# flashtest.net
KiCad netlist of a schematic drawn in EAGLE
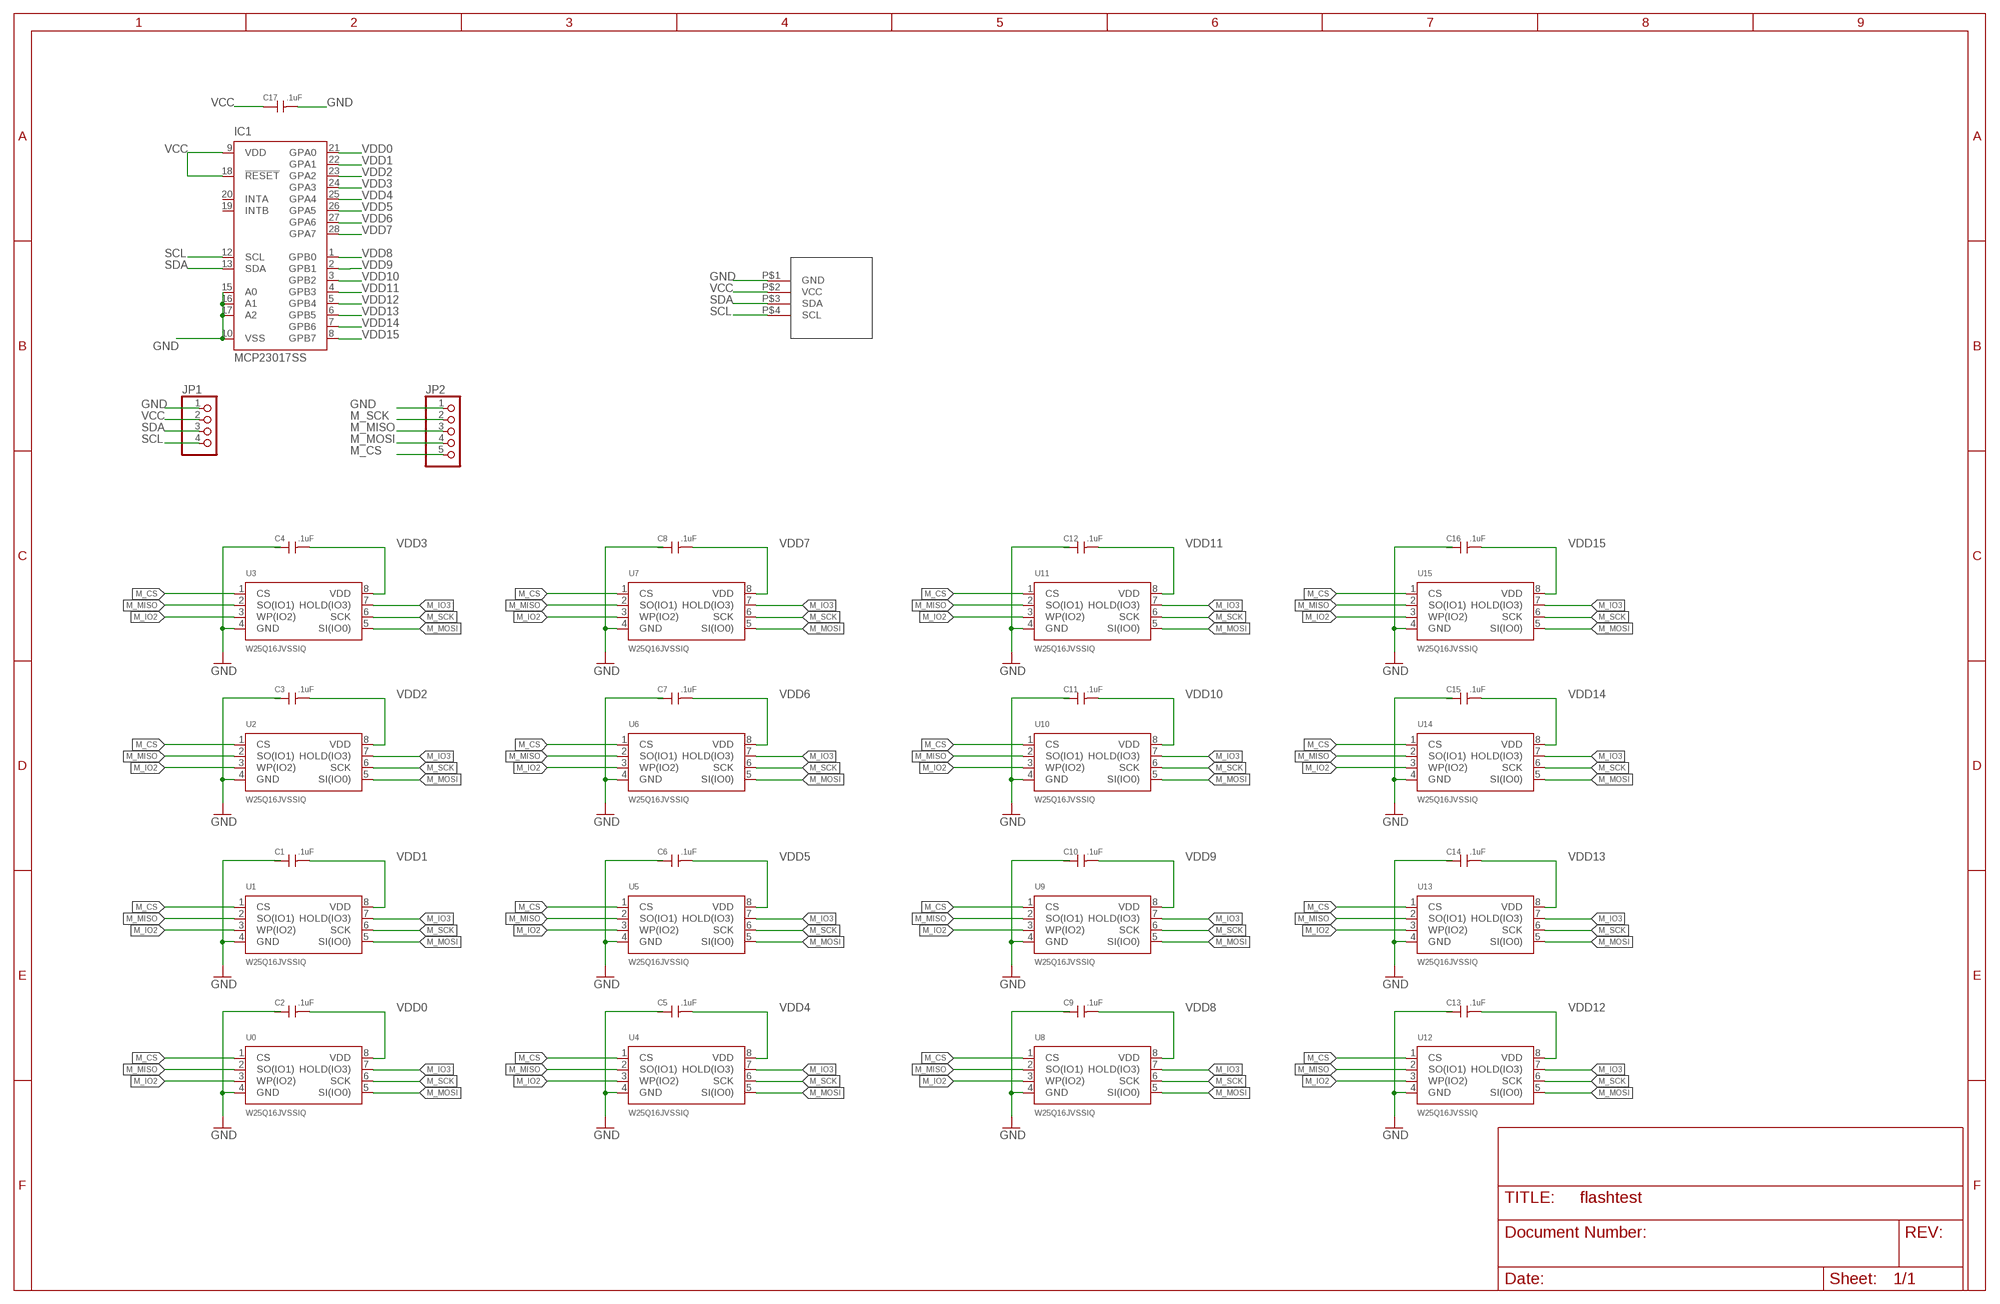
[diagram p0: schematic, sheet 1]

(export (version "E")
  (design (tool "Eeschema 10.0.6"))
  (components
    (comp (ref "C1")
      (value ".1uF")
      (footprint "eagle-import:0603@1")
      (libsource (lib "eagle-import") (part "006-C3540"))
    )
    (comp (ref "C2")
      (value ".1uF")
      (footprint "eagle-import:0603@1")
      (libsource (lib "eagle-import") (part "006-C3540"))
    )
    (comp (ref "C3")
      (value ".1uF")
      (footprint "eagle-import:0603@1")
      (libsource (lib "eagle-import") (part "006-C3540"))
    )
    (comp (ref "C4")
      (value ".1uF")
      (footprint "eagle-import:0603@1")
      (libsource (lib "eagle-import") (part "006-C3540"))
    )
    (comp (ref "C5")
      (value ".1uF")
      (footprint "eagle-import:0603@1")
      (libsource (lib "eagle-import") (part "006-C3540"))
    )
    (comp (ref "C6")
      (value ".1uF")
      (footprint "eagle-import:0603@1")
      (libsource (lib "eagle-import") (part "006-C3540"))
    )
    (comp (ref "C7")
      (value ".1uF")
      (footprint "eagle-import:0603@1")
      (libsource (lib "eagle-import") (part "006-C3540"))
    )
    (comp (ref "C8")
      (value ".1uF")
      (footprint "eagle-import:0603@1")
      (libsource (lib "eagle-import") (part "006-C3540"))
    )
    (comp (ref "C9")
      (value ".1uF")
      (footprint "eagle-import:0603@1")
      (libsource (lib "eagle-import") (part "006-C3540"))
    )
    (comp (ref "C10")
      (value ".1uF")
      (footprint "eagle-import:0603@1")
      (libsource (lib "eagle-import") (part "006-C3540"))
    )
    (comp (ref "C11")
      (value ".1uF")
      (footprint "eagle-import:0603@1")
      (libsource (lib "eagle-import") (part "006-C3540"))
    )
    (comp (ref "C12")
      (value ".1uF")
      (footprint "eagle-import:0603@1")
      (libsource (lib "eagle-import") (part "006-C3540"))
    )
    (comp (ref "C13")
      (value ".1uF")
      (footprint "eagle-import:0603@1")
      (libsource (lib "eagle-import") (part "006-C3540"))
    )
    (comp (ref "C14")
      (value ".1uF")
      (footprint "eagle-import:0603@1")
      (libsource (lib "eagle-import") (part "006-C3540"))
    )
    (comp (ref "C15")
      (value ".1uF")
      (footprint "eagle-import:0603@1")
      (libsource (lib "eagle-import") (part "006-C3540"))
    )
    (comp (ref "C16")
      (value ".1uF")
      (footprint "eagle-import:0603@1")
      (libsource (lib "eagle-import") (part "006-C3540"))
    )
    (comp (ref "C17")
      (value ".1uF")
      (footprint "eagle-import:0603@1")
      (libsource (lib "eagle-import") (part "006-C3540"))
    )
    (comp (ref "IC1")
      (value "MCP23017SS")
      (footprint "eagle-import:SSOP28")
      (fields (field (name "MF") "MICROCHIP") (field (name "MPN") "MCP23017-E/SS"))
      (libsource (lib "eagle-import") (part "MCP23017SS"))
    )
    (comp (ref "JP1")
      (value "PINHD-1X4")
      (footprint "eagle-import:1X04")
      (libsource (lib "eagle-import") (part "PINHD-1X4"))
    )
    (comp (ref "JP2")
      (value "PINHD-1X5")
      (footprint "eagle-import:1X05")
      (libsource (lib "eagle-import") (part "PINHD-1X5"))
    )
    (comp (ref "U$1")
      (value "I2C")
      (footprint "eagle-import:I2C")
      (libsource (lib "eagle-import") (part "I2C"))
    )
    (comp (ref "U0")
      (value "W25Q16JVSSIQ")
      (footprint "eagle-import:SOIC-8")
      (libsource (lib "eagle-import") (part "FLASH_QSPI"))
    )
    (comp (ref "U1")
      (value "W25Q16JVSSIQ")
      (footprint "eagle-import:SOIC-8")
      (libsource (lib "eagle-import") (part "FLASH_QSPI"))
    )
    (comp (ref "U2")
      (value "W25Q16JVSSIQ")
      (footprint "eagle-import:SOIC-8")
      (libsource (lib "eagle-import") (part "FLASH_QSPI"))
    )
    (comp (ref "U3")
      (value "W25Q16JVSSIQ")
      (footprint "eagle-import:SOIC-8")
      (libsource (lib "eagle-import") (part "FLASH_QSPI"))
    )
    (comp (ref "U4")
      (value "W25Q16JVSSIQ")
      (footprint "eagle-import:SOIC-8")
      (libsource (lib "eagle-import") (part "FLASH_QSPI"))
    )
    (comp (ref "U5")
      (value "W25Q16JVSSIQ")
      (footprint "eagle-import:SOIC-8")
      (libsource (lib "eagle-import") (part "FLASH_QSPI"))
    )
    (comp (ref "U6")
      (value "W25Q16JVSSIQ")
      (footprint "eagle-import:SOIC-8")
      (libsource (lib "eagle-import") (part "FLASH_QSPI"))
    )
    (comp (ref "U7")
      (value "W25Q16JVSSIQ")
      (footprint "eagle-import:SOIC-8")
      (libsource (lib "eagle-import") (part "FLASH_QSPI"))
    )
    (comp (ref "U8")
      (value "W25Q16JVSSIQ")
      (footprint "eagle-import:SOIC-8")
      (libsource (lib "eagle-import") (part "FLASH_QSPI"))
    )
    (comp (ref "U9")
      (value "W25Q16JVSSIQ")
      (footprint "eagle-import:SOIC-8")
      (libsource (lib "eagle-import") (part "FLASH_QSPI"))
    )
    (comp (ref "U10")
      (value "W25Q16JVSSIQ")
      (footprint "eagle-import:SOIC-8")
      (libsource (lib "eagle-import") (part "FLASH_QSPI"))
    )
    (comp (ref "U11")
      (value "W25Q16JVSSIQ")
      (footprint "eagle-import:SOIC-8")
      (libsource (lib "eagle-import") (part "FLASH_QSPI"))
    )
    (comp (ref "U12")
      (value "W25Q16JVSSIQ")
      (footprint "eagle-import:SOIC-8")
      (libsource (lib "eagle-import") (part "FLASH_QSPI"))
    )
    (comp (ref "U13")
      (value "W25Q16JVSSIQ")
      (footprint "eagle-import:SOIC-8")
      (libsource (lib "eagle-import") (part "FLASH_QSPI"))
    )
    (comp (ref "U14")
      (value "W25Q16JVSSIQ")
      (footprint "eagle-import:SOIC-8")
      (libsource (lib "eagle-import") (part "FLASH_QSPI"))
    )
    (comp (ref "U15")
      (value "W25Q16JVSSIQ")
      (footprint "eagle-import:SOIC-8")
      (libsource (lib "eagle-import") (part "FLASH_QSPI"))
    )
  )
  (nets
    (net (code "1") (name "/SCL") (class "Default")
      (node (ref "IC1") (pin "12") (pinfunction "SCL_12") (pintype "input"))
      (node (ref "JP1") (pin "4") (pinfunction "4_4") (pintype "passive"))
      (node (ref "U$1") (pin "P$4") (pinfunction "SCL_P$4") (pintype "bidirectional"))
    )
    (net (code "2") (name "/SDA") (class "Default")
      (node (ref "IC1") (pin "13") (pinfunction "SDA_13") (pintype "bidirectional"))
      (node (ref "JP1") (pin "3") (pinfunction "3_3") (pintype "passive"))
      (node (ref "U$1") (pin "P$3") (pinfunction "SDA_P$3") (pintype "bidirectional"))
    )
    (net (code "3") (name "/VCC") (class "Default")
      (node (ref "C17") (pin "1") (pinfunction "1_1") (pintype "passive"))
      (node (ref "IC1") (pin "18") (pinfunction "~{RESET}_18") (pintype "input"))
      (node (ref "IC1") (pin "9") (pinfunction "VDD_9") (pintype "power_in"))
      (node (ref "JP1") (pin "2") (pinfunction "2_2") (pintype "passive"))
      (node (ref "U$1") (pin "P$2") (pinfunction "VCC_P$2") (pintype "bidirectional"))
    )
    (net (code "4") (name "/VDD0") (class "Default")
      (node (ref "C2") (pin "2") (pinfunction "2_2") (pintype "passive"))
      (node (ref "IC1") (pin "21") (pinfunction "GPA0_21") (pintype "bidirectional"))
      (node (ref "U0") (pin "8") (pinfunction "VDD_8") (pintype "power_in"))
    )
    (net (code "5") (name "/VDD1") (class "Default")
      (node (ref "C1") (pin "2") (pinfunction "2_2") (pintype "passive"))
      (node (ref "IC1") (pin "22") (pinfunction "GPA1_22") (pintype "bidirectional"))
      (node (ref "U1") (pin "8") (pinfunction "VDD_8") (pintype "power_in"))
    )
    (net (code "6") (name "/VDD2") (class "Default")
      (node (ref "C3") (pin "2") (pinfunction "2_2") (pintype "passive"))
      (node (ref "IC1") (pin "23") (pinfunction "GPA2_23") (pintype "bidirectional"))
      (node (ref "U2") (pin "8") (pinfunction "VDD_8") (pintype "power_in"))
    )
    (net (code "7") (name "/VDD3") (class "Default")
      (node (ref "C4") (pin "2") (pinfunction "2_2") (pintype "passive"))
      (node (ref "IC1") (pin "24") (pinfunction "GPA3_24") (pintype "bidirectional"))
      (node (ref "U3") (pin "8") (pinfunction "VDD_8") (pintype "power_in"))
    )
    (net (code "8") (name "/VDD4") (class "Default")
      (node (ref "C5") (pin "2") (pinfunction "2_2") (pintype "passive"))
      (node (ref "IC1") (pin "25") (pinfunction "GPA4_25") (pintype "bidirectional"))
      (node (ref "U4") (pin "8") (pinfunction "VDD_8") (pintype "power_in"))
    )
    (net (code "9") (name "/VDD5") (class "Default")
      (node (ref "C6") (pin "2") (pinfunction "2_2") (pintype "passive"))
      (node (ref "IC1") (pin "26") (pinfunction "GPA5_26") (pintype "bidirectional"))
      (node (ref "U5") (pin "8") (pinfunction "VDD_8") (pintype "power_in"))
    )
    (net (code "10") (name "/VDD6") (class "Default")
      (node (ref "C7") (pin "2") (pinfunction "2_2") (pintype "passive"))
      (node (ref "IC1") (pin "27") (pinfunction "GPA6_27") (pintype "bidirectional"))
      (node (ref "U6") (pin "8") (pinfunction "VDD_8") (pintype "power_in"))
    )
    (net (code "11") (name "/VDD7") (class "Default")
      (node (ref "C8") (pin "2") (pinfunction "2_2") (pintype "passive"))
      (node (ref "IC1") (pin "28") (pinfunction "GPA7_28") (pintype "bidirectional"))
      (node (ref "U7") (pin "8") (pinfunction "VDD_8") (pintype "power_in"))
    )
    (net (code "12") (name "/VDD8") (class "Default")
      (node (ref "C9") (pin "2") (pinfunction "2_2") (pintype "passive"))
      (node (ref "IC1") (pin "1") (pinfunction "GPB0_1") (pintype "bidirectional"))
      (node (ref "U8") (pin "8") (pinfunction "VDD_8") (pintype "power_in"))
    )
    (net (code "13") (name "/VDD9") (class "Default")
      (node (ref "C10") (pin "2") (pinfunction "2_2") (pintype "passive"))
      (node (ref "IC1") (pin "2") (pinfunction "GPB1_2") (pintype "bidirectional"))
      (node (ref "U9") (pin "8") (pinfunction "VDD_8") (pintype "power_in"))
    )
    (net (code "14") (name "/VDD10") (class "Default")
      (node (ref "C11") (pin "2") (pinfunction "2_2") (pintype "passive"))
      (node (ref "IC1") (pin "3") (pinfunction "GPB2_3") (pintype "bidirectional"))
      (node (ref "U10") (pin "8") (pinfunction "VDD_8") (pintype "power_in"))
    )
    (net (code "15") (name "/VDD11") (class "Default")
      (node (ref "C12") (pin "2") (pinfunction "2_2") (pintype "passive"))
      (node (ref "IC1") (pin "4") (pinfunction "GPB3_4") (pintype "bidirectional"))
      (node (ref "U11") (pin "8") (pinfunction "VDD_8") (pintype "power_in"))
    )
    (net (code "16") (name "/VDD12") (class "Default")
      (node (ref "C13") (pin "2") (pinfunction "2_2") (pintype "passive"))
      (node (ref "IC1") (pin "5") (pinfunction "GPB4_5") (pintype "bidirectional"))
      (node (ref "U12") (pin "8") (pinfunction "VDD_8") (pintype "power_in"))
    )
    (net (code "17") (name "/VDD13") (class "Default")
      (node (ref "C14") (pin "2") (pinfunction "2_2") (pintype "passive"))
      (node (ref "IC1") (pin "6") (pinfunction "GPB5_6") (pintype "bidirectional"))
      (node (ref "U13") (pin "8") (pinfunction "VDD_8") (pintype "power_in"))
    )
    (net (code "18") (name "/VDD14") (class "Default")
      (node (ref "C15") (pin "2") (pinfunction "2_2") (pintype "passive"))
      (node (ref "IC1") (pin "7") (pinfunction "GPB6_7") (pintype "bidirectional"))
      (node (ref "U14") (pin "8") (pinfunction "VDD_8") (pintype "power_in"))
    )
    (net (code "19") (name "/VDD15") (class "Default")
      (node (ref "C16") (pin "2") (pinfunction "2_2") (pintype "passive"))
      (node (ref "IC1") (pin "8") (pinfunction "GPB7_8") (pintype "bidirectional"))
      (node (ref "U15") (pin "8") (pinfunction "VDD_8") (pintype "power_in"))
    )
    (net (code "20") (name "GND") (class "Default")
      (node (ref "C1") (pin "1") (pinfunction "1_1") (pintype "passive"))
      (node (ref "C10") (pin "1") (pinfunction "1_1") (pintype "passive"))
      (node (ref "C11") (pin "1") (pinfunction "1_1") (pintype "passive"))
      (node (ref "C12") (pin "1") (pinfunction "1_1") (pintype "passive"))
      (node (ref "C13") (pin "1") (pinfunction "1_1") (pintype "passive"))
      (node (ref "C14") (pin "1") (pinfunction "1_1") (pintype "passive"))
      (node (ref "C15") (pin "1") (pinfunction "1_1") (pintype "passive"))
      (node (ref "C16") (pin "1") (pinfunction "1_1") (pintype "passive"))
      (node (ref "C17") (pin "2") (pinfunction "2_2") (pintype "passive"))
      (node (ref "C2") (pin "1") (pinfunction "1_1") (pintype "passive"))
      (node (ref "C3") (pin "1") (pinfunction "1_1") (pintype "passive"))
      (node (ref "C4") (pin "1") (pinfunction "1_1") (pintype "passive"))
      (node (ref "C5") (pin "1") (pinfunction "1_1") (pintype "passive"))
      (node (ref "C6") (pin "1") (pinfunction "1_1") (pintype "passive"))
      (node (ref "C7") (pin "1") (pinfunction "1_1") (pintype "passive"))
      (node (ref "C8") (pin "1") (pinfunction "1_1") (pintype "passive"))
      (node (ref "C9") (pin "1") (pinfunction "1_1") (pintype "passive"))
      (node (ref "IC1") (pin "10") (pinfunction "VSS_10") (pintype "power_in"))
      (node (ref "IC1") (pin "15") (pinfunction "A0_15") (pintype "input"))
      (node (ref "IC1") (pin "16") (pinfunction "A1_16") (pintype "input"))
      (node (ref "IC1") (pin "17") (pinfunction "A2_17") (pintype "input"))
      (node (ref "JP1") (pin "1") (pinfunction "1_1") (pintype "passive"))
      (node (ref "JP2") (pin "1") (pinfunction "1_1") (pintype "passive"))
      (node (ref "U$1") (pin "P$1") (pinfunction "GND_P$1") (pintype "bidirectional"))
      (node (ref "U0") (pin "4") (pinfunction "GND_4") (pintype "power_in"))
      (node (ref "U1") (pin "4") (pinfunction "GND_4") (pintype "power_in"))
      (node (ref "U10") (pin "4") (pinfunction "GND_4") (pintype "power_in"))
      (node (ref "U11") (pin "4") (pinfunction "GND_4") (pintype "power_in"))
      (node (ref "U12") (pin "4") (pinfunction "GND_4") (pintype "power_in"))
      (node (ref "U13") (pin "4") (pinfunction "GND_4") (pintype "power_in"))
      (node (ref "U14") (pin "4") (pinfunction "GND_4") (pintype "power_in"))
      (node (ref "U15") (pin "4") (pinfunction "GND_4") (pintype "power_in"))
      (node (ref "U2") (pin "4") (pinfunction "GND_4") (pintype "power_in"))
      (node (ref "U3") (pin "4") (pinfunction "GND_4") (pintype "power_in"))
      (node (ref "U4") (pin "4") (pinfunction "GND_4") (pintype "power_in"))
      (node (ref "U5") (pin "4") (pinfunction "GND_4") (pintype "power_in"))
      (node (ref "U6") (pin "4") (pinfunction "GND_4") (pintype "power_in"))
      (node (ref "U7") (pin "4") (pinfunction "GND_4") (pintype "power_in"))
      (node (ref "U8") (pin "4") (pinfunction "GND_4") (pintype "power_in"))
      (node (ref "U9") (pin "4") (pinfunction "GND_4") (pintype "power_in"))
    )
    (net (code "21") (name "M_CS") (class "Default")
      (node (ref "JP2") (pin "5") (pinfunction "5_5") (pintype "passive"))
      (node (ref "U0") (pin "1") (pinfunction "CS_1") (pintype "input"))
      (node (ref "U1") (pin "1") (pinfunction "CS_1") (pintype "input"))
      (node (ref "U10") (pin "1") (pinfunction "CS_1") (pintype "input"))
      (node (ref "U11") (pin "1") (pinfunction "CS_1") (pintype "input"))
      (node (ref "U12") (pin "1") (pinfunction "CS_1") (pintype "input"))
      (node (ref "U13") (pin "1") (pinfunction "CS_1") (pintype "input"))
      (node (ref "U14") (pin "1") (pinfunction "CS_1") (pintype "input"))
      (node (ref "U15") (pin "1") (pinfunction "CS_1") (pintype "input"))
      (node (ref "U2") (pin "1") (pinfunction "CS_1") (pintype "input"))
      (node (ref "U3") (pin "1") (pinfunction "CS_1") (pintype "input"))
      (node (ref "U4") (pin "1") (pinfunction "CS_1") (pintype "input"))
      (node (ref "U5") (pin "1") (pinfunction "CS_1") (pintype "input"))
      (node (ref "U6") (pin "1") (pinfunction "CS_1") (pintype "input"))
      (node (ref "U7") (pin "1") (pinfunction "CS_1") (pintype "input"))
      (node (ref "U8") (pin "1") (pinfunction "CS_1") (pintype "input"))
      (node (ref "U9") (pin "1") (pinfunction "CS_1") (pintype "input"))
    )
    (net (code "22") (name "M_IO2") (class "Default")
      (node (ref "U0") (pin "3") (pinfunction "WP(IO2)_3") (pintype "input"))
      (node (ref "U1") (pin "3") (pinfunction "WP(IO2)_3") (pintype "input"))
      (node (ref "U10") (pin "3") (pinfunction "WP(IO2)_3") (pintype "input"))
      (node (ref "U11") (pin "3") (pinfunction "WP(IO2)_3") (pintype "input"))
      (node (ref "U12") (pin "3") (pinfunction "WP(IO2)_3") (pintype "input"))
      (node (ref "U13") (pin "3") (pinfunction "WP(IO2)_3") (pintype "input"))
      (node (ref "U14") (pin "3") (pinfunction "WP(IO2)_3") (pintype "input"))
      (node (ref "U15") (pin "3") (pinfunction "WP(IO2)_3") (pintype "input"))
      (node (ref "U2") (pin "3") (pinfunction "WP(IO2)_3") (pintype "input"))
      (node (ref "U3") (pin "3") (pinfunction "WP(IO2)_3") (pintype "input"))
      (node (ref "U4") (pin "3") (pinfunction "WP(IO2)_3") (pintype "input"))
      (node (ref "U5") (pin "3") (pinfunction "WP(IO2)_3") (pintype "input"))
      (node (ref "U6") (pin "3") (pinfunction "WP(IO2)_3") (pintype "input"))
      (node (ref "U7") (pin "3") (pinfunction "WP(IO2)_3") (pintype "input"))
      (node (ref "U8") (pin "3") (pinfunction "WP(IO2)_3") (pintype "input"))
      (node (ref "U9") (pin "3") (pinfunction "WP(IO2)_3") (pintype "input"))
    )
    (net (code "23") (name "M_IO3") (class "Default")
      (node (ref "U0") (pin "7") (pinfunction "HOLD(IO3)_7") (pintype "input"))
      (node (ref "U1") (pin "7") (pinfunction "HOLD(IO3)_7") (pintype "input"))
      (node (ref "U10") (pin "7") (pinfunction "HOLD(IO3)_7") (pintype "input"))
      (node (ref "U11") (pin "7") (pinfunction "HOLD(IO3)_7") (pintype "input"))
      (node (ref "U12") (pin "7") (pinfunction "HOLD(IO3)_7") (pintype "input"))
      (node (ref "U13") (pin "7") (pinfunction "HOLD(IO3)_7") (pintype "input"))
      (node (ref "U14") (pin "7") (pinfunction "HOLD(IO3)_7") (pintype "input"))
      (node (ref "U15") (pin "7") (pinfunction "HOLD(IO3)_7") (pintype "input"))
      (node (ref "U2") (pin "7") (pinfunction "HOLD(IO3)_7") (pintype "input"))
      (node (ref "U3") (pin "7") (pinfunction "HOLD(IO3)_7") (pintype "input"))
      (node (ref "U4") (pin "7") (pinfunction "HOLD(IO3)_7") (pintype "input"))
      (node (ref "U5") (pin "7") (pinfunction "HOLD(IO3)_7") (pintype "input"))
      (node (ref "U6") (pin "7") (pinfunction "HOLD(IO3)_7") (pintype "input"))
      (node (ref "U7") (pin "7") (pinfunction "HOLD(IO3)_7") (pintype "input"))
      (node (ref "U8") (pin "7") (pinfunction "HOLD(IO3)_7") (pintype "input"))
      (node (ref "U9") (pin "7") (pinfunction "HOLD(IO3)_7") (pintype "input"))
    )
    (net (code "24") (name "M_MISO") (class "Default")
      (node (ref "JP2") (pin "3") (pinfunction "3_3") (pintype "passive"))
      (node (ref "U0") (pin "2") (pinfunction "SO(IO1)_2") (pintype "output"))
      (node (ref "U1") (pin "2") (pinfunction "SO(IO1)_2") (pintype "output"))
      (node (ref "U10") (pin "2") (pinfunction "SO(IO1)_2") (pintype "output"))
      (node (ref "U11") (pin "2") (pinfunction "SO(IO1)_2") (pintype "output"))
      (node (ref "U12") (pin "2") (pinfunction "SO(IO1)_2") (pintype "output"))
      (node (ref "U13") (pin "2") (pinfunction "SO(IO1)_2") (pintype "output"))
      (node (ref "U14") (pin "2") (pinfunction "SO(IO1)_2") (pintype "output"))
      (node (ref "U15") (pin "2") (pinfunction "SO(IO1)_2") (pintype "output"))
      (node (ref "U2") (pin "2") (pinfunction "SO(IO1)_2") (pintype "output"))
      (node (ref "U3") (pin "2") (pinfunction "SO(IO1)_2") (pintype "output"))
      (node (ref "U4") (pin "2") (pinfunction "SO(IO1)_2") (pintype "output"))
      (node (ref "U5") (pin "2") (pinfunction "SO(IO1)_2") (pintype "output"))
      (node (ref "U6") (pin "2") (pinfunction "SO(IO1)_2") (pintype "output"))
      (node (ref "U7") (pin "2") (pinfunction "SO(IO1)_2") (pintype "output"))
      (node (ref "U8") (pin "2") (pinfunction "SO(IO1)_2") (pintype "output"))
      (node (ref "U9") (pin "2") (pinfunction "SO(IO1)_2") (pintype "output"))
    )
    (net (code "25") (name "M_MOSI") (class "Default")
      (node (ref "JP2") (pin "4") (pinfunction "4_4") (pintype "passive"))
      (node (ref "U0") (pin "5") (pinfunction "SI(IO0)_5") (pintype "output"))
      (node (ref "U1") (pin "5") (pinfunction "SI(IO0)_5") (pintype "output"))
      (node (ref "U10") (pin "5") (pinfunction "SI(IO0)_5") (pintype "output"))
      (node (ref "U11") (pin "5") (pinfunction "SI(IO0)_5") (pintype "output"))
      (node (ref "U12") (pin "5") (pinfunction "SI(IO0)_5") (pintype "output"))
      (node (ref "U13") (pin "5") (pinfunction "SI(IO0)_5") (pintype "output"))
      (node (ref "U14") (pin "5") (pinfunction "SI(IO0)_5") (pintype "output"))
      (node (ref "U15") (pin "5") (pinfunction "SI(IO0)_5") (pintype "output"))
      (node (ref "U2") (pin "5") (pinfunction "SI(IO0)_5") (pintype "output"))
      (node (ref "U3") (pin "5") (pinfunction "SI(IO0)_5") (pintype "output"))
      (node (ref "U4") (pin "5") (pinfunction "SI(IO0)_5") (pintype "output"))
      (node (ref "U5") (pin "5") (pinfunction "SI(IO0)_5") (pintype "output"))
      (node (ref "U6") (pin "5") (pinfunction "SI(IO0)_5") (pintype "output"))
      (node (ref "U7") (pin "5") (pinfunction "SI(IO0)_5") (pintype "output"))
      (node (ref "U8") (pin "5") (pinfunction "SI(IO0)_5") (pintype "output"))
      (node (ref "U9") (pin "5") (pinfunction "SI(IO0)_5") (pintype "output"))
    )
    (net (code "26") (name "M_SCK") (class "Default")
      (node (ref "JP2") (pin "2") (pinfunction "2_2") (pintype "passive"))
      (node (ref "U0") (pin "6") (pinfunction "SCK_6") (pintype "input"))
      (node (ref "U1") (pin "6") (pinfunction "SCK_6") (pintype "input"))
      (node (ref "U10") (pin "6") (pinfunction "SCK_6") (pintype "input"))
      (node (ref "U11") (pin "6") (pinfunction "SCK_6") (pintype "input"))
      (node (ref "U12") (pin "6") (pinfunction "SCK_6") (pintype "input"))
      (node (ref "U13") (pin "6") (pinfunction "SCK_6") (pintype "input"))
      (node (ref "U14") (pin "6") (pinfunction "SCK_6") (pintype "input"))
      (node (ref "U15") (pin "6") (pinfunction "SCK_6") (pintype "input"))
      (node (ref "U2") (pin "6") (pinfunction "SCK_6") (pintype "input"))
      (node (ref "U3") (pin "6") (pinfunction "SCK_6") (pintype "input"))
      (node (ref "U4") (pin "6") (pinfunction "SCK_6") (pintype "input"))
      (node (ref "U5") (pin "6") (pinfunction "SCK_6") (pintype "input"))
      (node (ref "U6") (pin "6") (pinfunction "SCK_6") (pintype "input"))
      (node (ref "U7") (pin "6") (pinfunction "SCK_6") (pintype "input"))
      (node (ref "U8") (pin "6") (pinfunction "SCK_6") (pintype "input"))
      (node (ref "U9") (pin "6") (pinfunction "SCK_6") (pintype "input"))
    )
    (net (code "27") (name "unconnected-(IC1-INTA-Pad20)") (class "Default")
      (node (ref "IC1") (pin "20") (pinfunction "INTA_20") (pintype "output"))
    )
    (net (code "28") (name "unconnected-(IC1-INTB-Pad19)") (class "Default")
      (node (ref "IC1") (pin "19") (pinfunction "INTB_19") (pintype "output"))
    )
  )
)
